# Power_Management.net
KiCad netlist of a schematic drawn in Altium Designer
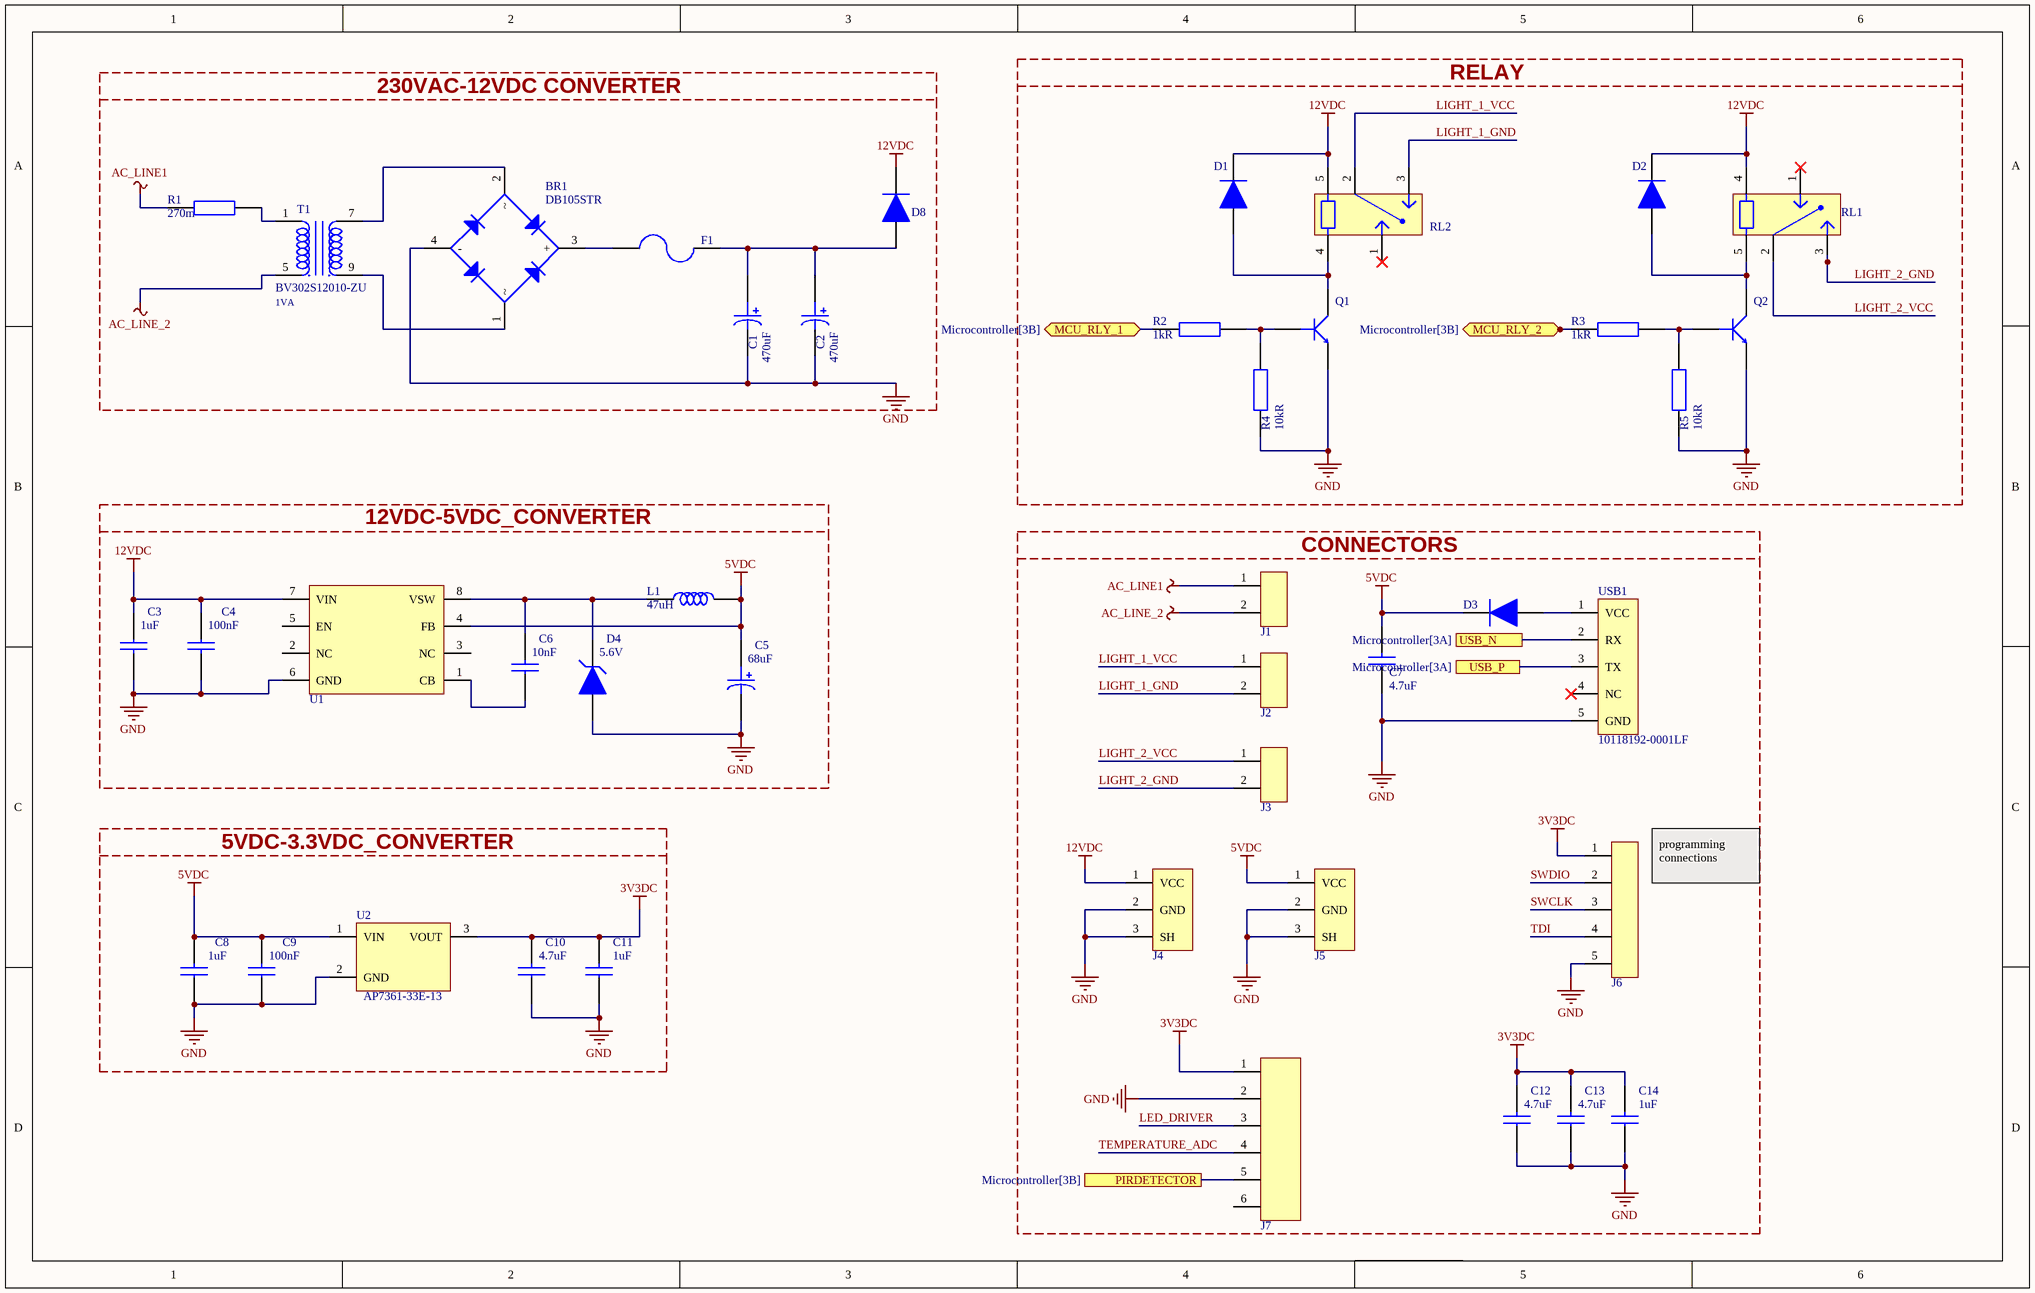
[diagram p0: Power Management.SchDoc]

(export (version "E")
  (design (tool "Eeschema 10.0.6"))
  (components
    (comp (ref "BR1")
      (value "DB105STR")
      (footprint "DB105STR")
      (description "Bridge Rect 1PHASE 600V 1A Db-s")
      (fields
        (field (name "MANUFACTURER") "Sangdest Microelectronics")
        (field (name "MANUFACTURER PART NUMBER") "DB105S")
        (field (name "DESIGNED BY") "Mustafa")
      )
      (libsource (lib "Mustafa_Library") (part "DB105STR"))
    )
    (comp (ref "C1")
      (value "ESH477M050AH4AA")
      (footprint "CAP_RADIAL_D10_P5")
      (description "CAP ALU ELEC 470uF 50V RADIAL")
      (fields
        (field (name "MANUFACTURER") "KEMET")
        (field (name "TOLERANCE") "20%")
        (field (name "CAPACITANCE") "470uF")
        (field (name "DESIGNED BY") "BERK")
      )
      (libsource (lib "Mustafa_Library") (part "CAP ALU ELEC 470uF 50V"))
    )
    (comp (ref "C2")
      (value "ESH477M050AH4AA")
      (footprint "CAP_RADIAL_D10_P5")
      (description "CAP ALU ELEC 470uF 50V RADIAL")
      (fields
        (field (name "MANUFACTURER") "KEMET")
        (field (name "TOLERANCE") "20%")
        (field (name "CAPACITANCE") "470uF")
        (field (name "DESIGNED BY") "BERK")
      )
      (libsource (lib "Mustafa_Library") (part "CAP ALU ELEC 470uF 50V"))
    )
    (comp (ref "C3")
      (value "CL21B105KBFNNNE")
      (footprint "CAP_0805")
      (description "CAP CER 1uF %10 0805")
      (fields
        (field (name "MANUFACTURER") "Samsung")
        (field (name "TOLERANCE") "10%")
        (field (name "CAPACITANCE") "1uF")
        (field (name "DESIGNED BY") "Mustafa")
      )
      (libsource (lib "Mustafa_Library") (part "CAP CER 1uF 0805"))
    )
    (comp (ref "C4")
      (value "CL21B104KBCNNNC")
      (footprint "CAP_0805")
      (description "CAP CER 100nF %10 0805")
      (fields
        (field (name "MANUFACTURER") "Samsung")
        (field (name "TOLERANCE") "10%")
        (field (name "CAPACITANCE") "100nF")
        (field (name "DESIGNED BY") "Mustafa")
      )
      (libsource (lib "Mustafa_Library") (part "CAP CER 100nF 0805"))
    )
    (comp (ref "C5")
      (value "EEV686M035A9HAA")
      (footprint "CAP_EEVseries")
      (description "Cap Aluminum Lytic 68uF 35V 20% (6.3 X 7.7mm) SMD 280mA 2000h 105C T/R")
      (fields
        (field (name "MANUFACTURER") "KEMET")
        (field (name "TOLERANCE") "20%")
        (field (name "CAPACITANCE") "68uF")
      )
      (libsource (lib "Mustafa_Library") (part "CAP ALU 68uF"))
    )
    (comp (ref "C6")
      (value "0603B103K160CT")
      (footprint "CAP_0603")
      (description "CAP CER 10nF %10 0603")
      (fields
        (field (name "MANUFACTURER") "Walsin Technologies")
        (field (name "TOLERANCE") "10%")
        (field (name "CAPACITANCE") "10nF")
        (field (name "DESIGNED BY") "Mustafa")
      )
      (libsource (lib "Mustafa_Library") (part "CAP CER 10nF 0603"))
    )
    (comp (ref "C7")
      (value "CL21A475KAQNNNE")
      (footprint "CAP_0805")
      (description "CAP CER 4.7uF %10 0805")
      (fields
        (field (name "MANUFACTURER") "Samsung")
        (field (name "TOLERANCE") "10%")
        (field (name "CAPACITANCE") "4.7uF")
        (field (name "DESIGNED BY") "Mustafa")
      )
      (libsource (lib "Mustafa_Library") (part "CAP CER 4.7uF 0805"))
    )
    (comp (ref "C8")
      (value "CL21B105KBFNNNE")
      (footprint "CAP_0805")
      (description "CAP CER 1uF %10 0805")
      (fields
        (field (name "MANUFACTURER") "Samsung")
        (field (name "TOLERANCE") "10%")
        (field (name "CAPACITANCE") "1uF")
        (field (name "DESIGNED BY") "Mustafa")
      )
      (libsource (lib "Mustafa_Library") (part "CAP CER 1uF 0805"))
    )
    (comp (ref "C9")
      (value "CL21B104KBCNNNC")
      (footprint "CAP_0805")
      (description "CAP CER 100nF %10 0805")
      (fields
        (field (name "MANUFACTURER") "Samsung")
        (field (name "TOLERANCE") "10%")
        (field (name "CAPACITANCE") "100nF")
        (field (name "DESIGNED BY") "Mustafa")
      )
      (libsource (lib "Mustafa_Library") (part "CAP CER 100nF 0805"))
    )
    (comp (ref "C10")
      (value "CL21A475KAQNNNE")
      (footprint "CAP_0805")
      (description "CAP CER 4.7uF %10 0805")
      (fields
        (field (name "MANUFACTURER") "Samsung")
        (field (name "TOLERANCE") "10%")
        (field (name "CAPACITANCE") "4.7uF")
        (field (name "DESIGNED BY") "Mustafa")
      )
      (libsource (lib "Mustafa_Library") (part "CAP CER 4.7uF 0805"))
    )
    (comp (ref "C11")
      (value "CL21B105KBFNNNE")
      (footprint "CAP_0805")
      (description "CAP CER 1uF %10 0805")
      (fields
        (field (name "MANUFACTURER") "Samsung")
        (field (name "TOLERANCE") "10%")
        (field (name "CAPACITANCE") "1uF")
        (field (name "DESIGNED BY") "Mustafa")
      )
      (libsource (lib "Mustafa_Library") (part "CAP CER 1uF 0805"))
    )
    (comp (ref "C12")
      (value "CL21A475KAQNNNE")
      (footprint "CAP_0805")
      (description "CAP CER 4.7uF %10 0805")
      (fields
        (field (name "MANUFACTURER") "Samsung")
        (field (name "TOLERANCE") "10%")
        (field (name "CAPACITANCE") "4.7uF")
        (field (name "DESIGNED BY") "Mustafa")
      )
      (libsource (lib "Mustafa_Library") (part "CAP CER 4.7uF 0805"))
    )
    (comp (ref "C13")
      (value "CL21A475KAQNNNE")
      (footprint "CAP_0805")
      (description "CAP CER 4.7uF %10 0805")
      (fields
        (field (name "MANUFACTURER") "Samsung")
        (field (name "TOLERANCE") "10%")
        (field (name "CAPACITANCE") "4.7uF")
        (field (name "DESIGNED BY") "Mustafa")
      )
      (libsource (lib "Mustafa_Library") (part "CAP CER 4.7uF 0805"))
    )
    (comp (ref "C14")
      (value "CL21B105KBFNNNE")
      (footprint "CAP_0805")
      (description "CAP CER 1uF %10 0805")
      (fields
        (field (name "MANUFACTURER") "Samsung")
        (field (name "TOLERANCE") "10%")
        (field (name "CAPACITANCE") "1uF")
        (field (name "DESIGNED BY") "Mustafa")
      )
      (libsource (lib "Mustafa_Library") (part "CAP CER 1uF 0805"))
    )
    (comp (ref "D1")
      (value "1N4148WS")
      (footprint "SOD323F")
      (description "Diode, Single, 75 V, 150 mA, 1 V, 4 ns")
      (fields
        (field (name "MANUFACTURER") "ON Semiconductor / Fairchild")
        (field (name "DESIGNED BY") "BERK")
      )
      (libsource (lib "Mustafa_Library") (part "1N4148WS"))
    )
    (comp (ref "D2")
      (value "1N4148WS")
      (footprint "SOD323F")
      (description "Diode, Single, 75 V, 150 mA, 1 V, 4 ns")
      (fields
        (field (name "MANUFACTURER") "ON Semiconductor / Fairchild")
        (field (name "DESIGNED BY") "BERK")
      )
      (libsource (lib "Mustafa_Library") (part "1N4148WS"))
    )
    (comp (ref "D3")
      (value "1N4148WS")
      (footprint "SOD323F")
      (description "Diode, Single, 75 V, 150 mA, 1 V, 4 ns")
      (fields
        (field (name "MANUFACTURER") "ON Semiconductor / Fairchild")
        (field (name "DESIGNED BY") "BERK")
      )
      (libsource (lib "Mustafa_Library") (part "1N4148WS"))
    )
    (comp (ref "D4")
      (value "1SMB5919BT3G")
      (footprint "SMB")
      (description "Diode Zener Single 5.6V 5% 3W 2-Pin SMB T/R")
      (fields
        (field (name "MANUFACTURER") "ON Semiconductor")
        (field (name "TOLERANCE") "5%")
        (field (name "WORKING VOLTAGE") "5.6V")
        (field (name "DESIGNED BY") "Mustafa")
      )
      (libsource (lib "Mustafa_Library") (part "1SMB5919BT3G"))
    )
    (comp (ref "D8")
      (value "1N4148WS")
      (footprint "SOD323F")
      (description "Diode, Single, 75 V, 150 mA, 1 V, 4 ns")
      (fields
        (field (name "MANUFACTURER") "ON Semiconductor / Fairchild")
        (field (name "DESIGNED BY") "BERK")
      )
      (libsource (lib "Mustafa_Library") (part "1N4148WS"))
    )
    (comp (ref "F1")
      (value "3413.0216.22")
      (footprint "3413.0216.22 (sigorta)")
      (description "FUSE BRD MNT 1A 32VAC 63VDC 1206")
      (fields (field (name "MANUFACTURER") "Schurter") (field (name "DESIGNED BY") "BERK"))
      (libsource (lib "Mustafa_Library") (part "FUSE 3413.0216.22"))
    )
    (comp (ref "J1")
      (value "TBP01R1-508-02BE")
      (footprint "TBP01R1-508")
      (description "Conn Shrouded Header HDR 2 POS 5.08mm Solder RA Side Entry Thru-Hole Bag")
      (fields (field (name "MANUFACTURER") "CUI") (field (name "DESIGNED BY") "BERK"))
      (libsource (lib "Mustafa_Library") (part "TBP01R1-508-02BE"))
    )
    (comp (ref "J2")
      (value "TBP01R1-508-02BE")
      (footprint "TBP01R1-508")
      (description "Conn Shrouded Header HDR 2 POS 5.08mm Solder RA Side Entry Thru-Hole Bag")
      (fields (field (name "MANUFACTURER") "CUI") (field (name "DESIGNED BY") "BERK"))
      (libsource (lib "Mustafa_Library") (part "TBP01R1-508-02BE"))
    )
    (comp (ref "J3")
      (value "TBP01R1-508-02BE")
      (footprint "TBP01R1-508")
      (description "Conn Shrouded Header HDR 2 POS 5.08mm Solder RA Side Entry Thru-Hole Bag")
      (fields (field (name "MANUFACTURER") "CUI") (field (name "DESIGNED BY") "BERK"))
      (libsource (lib "Mustafa_Library") (part "TBP01R1-508-02BE"))
    )
    (comp (ref "J4")
      (value "PJ-037AH-SMT-TR")
      (footprint "JACK")
      (description "DC Power Connectors Power Jacks")
      (fields (field (name "MANUFACTURER") "CUI") (field (name "DESIGNED BY") "BERK"))
      (libsource (lib "Mustafa_Library") (part "PJ-037AH-SMT-TR"))
    )
    (comp (ref "J5")
      (value "PJ-037AH-SMT-TR")
      (footprint "JACK")
      (description "DC Power Connectors Power Jacks")
      (fields (field (name "MANUFACTURER") "CUI") (field (name "DESIGNED BY") "BERK"))
      (libsource (lib "Mustafa_Library") (part "PJ-037AH-SMT-TR"))
    )
    (comp (ref "J6")
      (value "SMH-105-02-L-S")
      (footprint "PINHEADER1X5_RA")
      (description ".100 C.L. HORIZONTAL SMT SOCKET")
      (fields (field (name "MANUFACTURER") "Samtec") (field (name "DESIGNED BY") "BERK"))
      (libsource (lib "Mustafa_Library") (part "SMH-105-02-L-S"))
    )
    (comp (ref "J7")
      (value "64800611622")
      (footprint "64800611622")
      (description "1.50mm 6PIN Connector")
      (fields (field (name "MANUFACTURER") "Wurth Electronics"))
      (libsource (lib "Mustafa_Library") (part "64800611622_conn_6pin"))
    )
    (comp (ref "L1")
      (value "78438335470")
      (footprint "IND_1212")
      (description "FIXED IND 47UH 390MA 2.3 OHM SMD")
      (fields
        (field (name "MANUFACTURER") "Wurth Electronics")
        (field (name "TOLERANCE") "30%")
        (field (name "INDUCTANCE") "47uH")
        (field (name "DESIGNED BY") "Mustafa")
      )
      (libsource (lib "Mustafa_Library") (part "IND 47uH"))
    )
    (comp (ref "Q1")
      (value "MMBT3904-7-F")
      (footprint "SOT-23F")
      (description "Transistor General Purpose BJT NPN 40 Volt 0.2A Automotive 3-Pin SOT-23")
      (fields (field (name "MANUFACTURER") "Diodes Zetex") (field (name "DESIGNED BY") "Mustafa"))
      (libsource (lib "Mustafa_Library") (part "MMBT3904-7-F"))
    )
    (comp (ref "Q2")
      (value "MMBT3904-7-F")
      (footprint "SOT-23F")
      (description "Transistor General Purpose BJT NPN 40 Volt 0.2A Automotive 3-Pin SOT-23")
      (fields (field (name "MANUFACTURER") "Diodes Zetex") (field (name "DESIGNED BY") "Mustafa"))
      (libsource (lib "Mustafa_Library") (part "MMBT3904-7-F"))
    )
    (comp (ref "R1")
      (value "5WD27")
      (footprint "RES_AXIAL_W")
      (description "Resistor 5 Watt Cermet Wirewound Flameproof .27 Ohm 5% Axial Lead")
      (fields
        (field (name "MANUFACTURER") "NTE Electronics")
        (field (name "TOLERANCE") "5%")
        (field (name "RESISTANCE") "270m")
        (field (name "DESIGNED BY") "Mustafa")
      )
      (libsource (lib "Mustafa_Library") (part "5WD27"))
    )
    (comp (ref "R2")
      (value "RC0603FR-0710KL")
      (footprint "RES_0603")
      (description "RES 1K %1 OHM 0603 SMD")
      (fields
        (field (name "MANUFACTURER") "Yageo")
        (field (name "MANUFACTURER PART NUMBER") "RC0603JR-071KL")
        (field (name "RESISTANCE") "1kR")
        (field (name "DESIGNED BY") "BERK")
      )
      (libsource (lib "Mustafa_Library") (part "RES 1K OHM 0603"))
    )
    (comp (ref "R3")
      (value "RC0603FR-0710KL")
      (footprint "RES_0603")
      (description "RES 1K %1 OHM 0603 SMD")
      (fields
        (field (name "MANUFACTURER") "Yageo")
        (field (name "MANUFACTURER PART NUMBER") "RC0603JR-071KL")
        (field (name "RESISTANCE") "1kR")
        (field (name "DESIGNED BY") "BERK")
      )
      (libsource (lib "Mustafa_Library") (part "RES 1K OHM 0603"))
    )
    (comp (ref "R4")
      (value "10kR")
      (footprint "RES_0603")
      (description "RES 10K %1 OHM 0603 SMD")
      (fields
        (field (name "MANUFACTURER") "Yageo")
        (field (name "MANUFACTURER PART NUMBER") "RC0603FR-0710KL")
        (field (name "DESIGNED BY") "Mustafa")
      )
      (libsource (lib "Mustafa_Library") (part "RES 10K OHM 0603"))
    )
    (comp (ref "R5")
      (value "10kR")
      (footprint "RES_0603")
      (description "RES 10K %1 OHM 0603 SMD")
      (fields
        (field (name "MANUFACTURER") "Yageo")
        (field (name "MANUFACTURER PART NUMBER") "RC0603FR-0710KL")
        (field (name "DESIGNED BY") "Mustafa")
      )
      (libsource (lib "Mustafa_Library") (part "RES 10K OHM 0603"))
    )
    (comp (ref "RL1")
      (value "ALQ112")
      (footprint "ALQ112")
      (description "General Purpose Relay SPDT (1 Form C) 12VDC Coil Through Hole")
      (fields (field (name "MANUFACTURER") "Panasonic") (field (name "DESIGNED BY") "Mustafa"))
      (libsource (lib "") (part "ALQ112_1"))
    )
    (comp (ref "RL2")
      (value "ALQ112")
      (footprint "ALQ112")
      (description "General Purpose Relay SPDT (1 Form C) 12VDC Coil Through Hole")
      (fields (field (name "MANUFACTURER") "Panasonic") (field (name "DESIGNED BY") "Mustafa"))
      (libsource (lib "Mustafa_Library") (part "ALQ112"))
    )
    (comp (ref "T1")
      (value "BV302S12010-ZU")
      (footprint "BV302S")
      (description "230-12V Transformer 1VA")
      (fields
        (field (name "MANUFACTURER PRODUCT NUMBER") "BV302S12010-ZU")
        (field (name "MANUFACTURER") "Zettler Magnetics")
        (field (name "RATED POWER") "1VA")
        (field (name "DESIGNED BY") "Mustafa")
      )
      (libsource (lib "Mustafa_Library") (part "BV302S12010-ZU"))
    )
    (comp (ref "U1")
      (value "LM2675MX-12/NOPB")
      (footprint "SOIC-8")
      (description "SIMPLE SWITCHER® 6.5V to 40V, 1A Low Component Count Step-Down Regulator 8-SOIC -40 to 125")
      (fields
        (field (name "MANUFACTURER") "TI National Semiconductor")
        (field (name "DESIGNED BY") "Mustafa")
      )
      (libsource (lib "Mustafa_Library") (part "LM2675MX-12/NOPB"))
    )
    (comp (ref "U2")
      (value "AP7361-33E-13")
      (footprint "SOT-223")
      (description "AP7361 Series 3.3 V 1 A Low SMT Dropout Fixed-Mode Regulator - SOT-223")
      (fields (field (name "MANUFACTURER") "Diodes") (field (name "DESIGNED BY") "Mustafa"))
      (libsource (lib "Mustafa_Library") (part "AP7361-33E-13"))
    )
    (comp (ref "USB1")
      (value "10118192-0001LF")
      (footprint "MICRO_B_USB")
      (description "CONN RCPT USB2.0 MICRO B SMD R/A")
      (fields (field (name "MANUFACTURER") "Amphenol FCI") (field (name "DESIGNED BY") "BERK"))
      (libsource (lib "Mustafa_Library") (part "Micro B USB Connector"))
    )
  )
  (nets
    (net (code "1") (name "/LED_DRIVER") (class "Default") (node (ref "J7") (pin "3") (pintype "power_in")))
    (net (code "2") (name "/LIGHT_1_GND") (class "Default")
      (node (ref "J2") (pin "2") (pinfunction "2_2") (pintype "power_in"))
      (node (ref "RL2") (pin "3") (pinfunction "3_3") (pintype "passive"))
    )
    (net (code "3") (name "/LIGHT_1_VCC") (class "Default")
      (node (ref "J2") (pin "1") (pinfunction "1_1") (pintype "power_in"))
      (node (ref "RL2") (pin "2") (pinfunction "2_2") (pintype "passive"))
    )
    (net (code "4") (name "/LIGHT_2_GND") (class "Default")
      (node (ref "J3") (pin "2") (pinfunction "2_2") (pintype "power_in"))
      (node (ref "RL1") (pin "3") (pinfunction "3_3") (pintype "passive"))
    )
    (net (code "5") (name "/LIGHT_2_VCC") (class "Default")
      (node (ref "J3") (pin "1") (pinfunction "1_1") (pintype "power_in"))
      (node (ref "RL1") (pin "2") (pinfunction "2_2") (pintype "passive"))
    )
    (net (code "6") (name "/MCU_RLY_1") (class "Default")
      (node (ref "R2") (pin "1") (pinfunction "1_1") (pintype "passive"))
    )
    (net (code "7") (name "/MCU_RLY_2") (class "Default")
      (node (ref "R3") (pin "1") (pinfunction "1_1") (pintype "passive"))
    )
    (net (code "8") (name "/PIRDETECTOR") (class "Default") (node (ref "J7") (pin "5") (pintype "power_in")))
    (net (code "9") (name "/SWCLK") (class "Default")
      (node (ref "J6") (pin "3") (pinfunction "3_3") (pintype "power_in"))
    )
    (net (code "10") (name "/SWDIO") (class "Default")
      (node (ref "J6") (pin "2") (pinfunction "2_2") (pintype "power_in"))
    )
    (net (code "11") (name "/TDI") (class "Default")
      (node (ref "J6") (pin "4") (pinfunction "4_4") (pintype "power_in"))
    )
    (net (code "12") (name "/TEMPERATURE_ADC") (class "Default")
      (node (ref "J7") (pin "4") (pintype "power_in"))
    )
    (net (code "13") (name "/USB_N") (class "Default")
      (node (ref "USB1") (pin "2") (pinfunction "RX_2") (pintype "power_in"))
    )
    (net (code "14") (name "/USB_P") (class "Default")
      (node (ref "USB1") (pin "3") (pinfunction "TX_3") (pintype "power_in"))
    )
    (net (code "15") (name "3V3DC") (class "Default")
      (node (ref "C10") (pin "2") (pinfunction "2_2") (pintype "passive"))
      (node (ref "C11") (pin "2") (pinfunction "2_2") (pintype "passive"))
      (node (ref "C12") (pin "2") (pinfunction "2_2") (pintype "passive"))
      (node (ref "C13") (pin "2") (pinfunction "2_2") (pintype "passive"))
      (node (ref "C14") (pin "2") (pinfunction "2_2") (pintype "passive"))
      (node (ref "J6") (pin "1") (pinfunction "1_1") (pintype "power_in"))
      (node (ref "J7") (pin "1") (pintype "power_in"))
      (node (ref "U2") (pin "3") (pinfunction "VOUT_3") (pintype "passive"))
    )
    (net (code "16") (name "5VDC") (class "Default")
      (node (ref "C5") (pin "1") (pinfunction "1_1") (pintype "passive"))
      (node (ref "C7") (pin "2") (pinfunction "2_2") (pintype "passive"))
      (node (ref "C8") (pin "2") (pinfunction "2_2") (pintype "passive"))
      (node (ref "C9") (pin "2") (pinfunction "2_2") (pintype "passive"))
      (node (ref "D3") (pin "1") (pinfunction "1_1") (pintype "power_in"))
      (node (ref "J5") (pin "1") (pinfunction "VCC_1") (pintype "power_in"))
      (node (ref "L1") (pin "2") (pinfunction "2_2") (pintype "passive"))
      (node (ref "U1") (pin "4") (pinfunction "FB_4") (pintype "passive"))
      (node (ref "U2") (pin "1") (pinfunction "VIN_1") (pintype "passive"))
    )
    (net (code "17") (name "12VDC") (class "Default")
      (node (ref "C3") (pin "1") (pinfunction "1_1") (pintype "passive"))
      (node (ref "C4") (pin "1") (pinfunction "1_1") (pintype "passive"))
      (node (ref "D1") (pin "1") (pinfunction "1_1") (pintype "power_in"))
      (node (ref "D2") (pin "1") (pinfunction "1_1") (pintype "power_in"))
      (node (ref "D8") (pin "1") (pinfunction "1_1") (pintype "power_in"))
      (node (ref "J4") (pin "1") (pinfunction "VCC_1") (pintype "power_in"))
      (node (ref "RL1") (pin "4") (pinfunction "4_4") (pintype "passive"))
      (node (ref "RL2") (pin "5") (pinfunction "5_5") (pintype "passive"))
      (node (ref "U1") (pin "7") (pinfunction "VIN_7") (pintype "passive"))
    )
    (net (code "18") (name "AC_LINE1") (class "Default")
      (node (ref "J1") (pin "1") (pinfunction "1_1") (pintype "power_in"))
      (node (ref "R1") (pin "1") (pinfunction "1_1") (pintype "passive"))
    )
    (net (code "19") (name "AC_LINE_2") (class "Default")
      (node (ref "J1") (pin "2") (pinfunction "2_2") (pintype "power_in"))
      (node (ref "T1") (pin "5") (pinfunction "5_5") (pintype "passive"))
    )
    (net (code "20") (name "GND") (class "Default")
      (node (ref "BR1") (pin "4") (pinfunction "-_4") (pintype "passive"))
      (node (ref "C1") (pin "2") (pinfunction "2_2") (pintype "passive"))
      (node (ref "C10") (pin "1") (pinfunction "1_1") (pintype "passive"))
      (node (ref "C11") (pin "1") (pinfunction "1_1") (pintype "passive"))
      (node (ref "C12") (pin "1") (pinfunction "1_1") (pintype "passive"))
      (node (ref "C13") (pin "1") (pinfunction "1_1") (pintype "passive"))
      (node (ref "C14") (pin "1") (pinfunction "1_1") (pintype "passive"))
      (node (ref "C2") (pin "2") (pinfunction "2_2") (pintype "passive"))
      (node (ref "C3") (pin "2") (pinfunction "2_2") (pintype "passive"))
      (node (ref "C4") (pin "2") (pinfunction "2_2") (pintype "passive"))
      (node (ref "C5") (pin "2") (pinfunction "2_2") (pintype "passive"))
      (node (ref "C7") (pin "1") (pinfunction "1_1") (pintype "passive"))
      (node (ref "C8") (pin "1") (pinfunction "1_1") (pintype "passive"))
      (node (ref "C9") (pin "1") (pinfunction "1_1") (pintype "passive"))
      (node (ref "D4") (pin "A") (pinfunction "A_A") (pintype "passive"))
      (node (ref "J4") (pin "2") (pinfunction "GND_2") (pintype "power_in"))
      (node (ref "J4") (pin "3") (pinfunction "SH_3") (pintype "power_in"))
      (node (ref "J5") (pin "2") (pinfunction "GND_2") (pintype "power_in"))
      (node (ref "J5") (pin "3") (pinfunction "SH_3") (pintype "power_in"))
      (node (ref "J6") (pin "5") (pinfunction "5_5") (pintype "power_in"))
      (node (ref "J7") (pin "2") (pintype "power_in"))
      (node (ref "Q1") (pin "2") (pinfunction "E_2") (pintype "power_in"))
      (node (ref "Q2") (pin "2") (pinfunction "E_2") (pintype "power_in"))
      (node (ref "R4") (pin "1") (pinfunction "1_1") (pintype "passive"))
      (node (ref "R5") (pin "1") (pinfunction "1_1") (pintype "passive"))
      (node (ref "U1") (pin "6") (pinfunction "GND_6") (pintype "passive"))
      (node (ref "U2") (pin "2") (pinfunction "GND_2") (pintype "passive"))
      (node (ref "USB1") (pin "5") (pinfunction "GND_5") (pintype "power_in"))
    )
    (net (code "21") (name "Net-(BR1-+)") (class "Default")
      (node (ref "BR1") (pin "3") (pinfunction "+_3") (pintype "passive"))
      (node (ref "F1") (pin "1") (pinfunction "1_1") (pintype "passive"))
    )
    (net (code "22") (name "Net-(BR1-~-Pad1)") (class "Default")
      (node (ref "BR1") (pin "1") (pinfunction "~_1") (pintype "passive"))
      (node (ref "T1") (pin "9") (pinfunction "9_9") (pintype "passive"))
    )
    (net (code "23") (name "Net-(BR1-~-Pad2)") (class "Default")
      (node (ref "BR1") (pin "2") (pinfunction "~_2") (pintype "passive"))
      (node (ref "T1") (pin "7") (pinfunction "7_7") (pintype "passive"))
    )
    (net (code "24") (name "Net-(C1-Pad1)") (class "Default")
      (node (ref "C1") (pin "1") (pinfunction "1_1") (pintype "passive"))
      (node (ref "C2") (pin "1") (pinfunction "1_1") (pintype "passive"))
      (node (ref "D8") (pin "2") (pinfunction "2_2") (pintype "power_in"))
      (node (ref "F1") (pin "2") (pinfunction "2_2") (pintype "passive"))
    )
    (net (code "25") (name "Net-(Q1-B)") (class "Default")
      (node (ref "Q1") (pin "1") (pinfunction "B_1") (pintype "power_in"))
      (node (ref "R2") (pin "2") (pinfunction "2_2") (pintype "passive"))
      (node (ref "R4") (pin "2") (pinfunction "2_2") (pintype "passive"))
    )
    (net (code "26") (name "Net-(Q1-C)") (class "Default")
      (node (ref "D1") (pin "2") (pinfunction "2_2") (pintype "power_in"))
      (node (ref "Q1") (pin "3") (pinfunction "C_3") (pintype "power_in"))
      (node (ref "RL2") (pin "4") (pinfunction "4_4") (pintype "passive"))
    )
    (net (code "27") (name "Net-(Q2-B)") (class "Default")
      (node (ref "Q2") (pin "1") (pinfunction "B_1") (pintype "power_in"))
      (node (ref "R3") (pin "2") (pinfunction "2_2") (pintype "passive"))
      (node (ref "R5") (pin "2") (pinfunction "2_2") (pintype "passive"))
    )
    (net (code "28") (name "Net-(Q2-C)") (class "Default")
      (node (ref "D2") (pin "2") (pinfunction "2_2") (pintype "power_in"))
      (node (ref "Q2") (pin "3") (pinfunction "C_3") (pintype "power_in"))
      (node (ref "RL1") (pin "5") (pinfunction "5_5") (pintype "passive"))
    )
    (net (code "29") (name "Net-(R1-Pad2)") (class "Default")
      (node (ref "R1") (pin "2") (pinfunction "2_2") (pintype "passive"))
      (node (ref "T1") (pin "1") (pinfunction "1_1") (pintype "passive"))
    )
    (net (code "30") (name "Net-(U1-CB)") (class "Default")
      (node (ref "C6") (pin "1") (pinfunction "1_1") (pintype "passive"))
      (node (ref "U1") (pin "1") (pinfunction "CB_1") (pintype "passive"))
    )
    (net (code "31") (name "Net-(U1-VSW)") (class "Default")
      (node (ref "C6") (pin "2") (pinfunction "2_2") (pintype "passive"))
      (node (ref "D4") (pin "C") (pinfunction "C_C") (pintype "passive"))
      (node (ref "L1") (pin "1") (pinfunction "1_1") (pintype "passive"))
      (node (ref "U1") (pin "8") (pinfunction "VSW_8") (pintype "passive"))
    )
    (net (code "32") (name "Net-(USB1-VCC)") (class "Default")
      (node (ref "D3") (pin "2") (pinfunction "2_2") (pintype "power_in"))
      (node (ref "USB1") (pin "1") (pinfunction "VCC_1") (pintype "power_in"))
    )
    (net (code "33") (name "unconnected-(J7-Pad6)") (class "Default")
      (node (ref "J7") (pin "6") (pintype "power_in"))
    )
    (net (code "34") (name "unconnected-(RL1-Pad1)") (class "Default")
      (node (ref "RL1") (pin "1") (pinfunction "1_1") (pintype "passive+no_connect"))
    )
    (net (code "35") (name "unconnected-(RL2-Pad1)") (class "Default")
      (node (ref "RL2") (pin "1") (pinfunction "1_1") (pintype "passive+no_connect"))
    )
    (net (code "36") (name "unconnected-(U1-EN-Pad5)") (class "Default")
      (node (ref "U1") (pin "5") (pinfunction "EN_5") (pintype "passive"))
    )
    (net (code "37") (name "unconnected-(U1-NC-Pad2)") (class "Default")
      (node (ref "U1") (pin "2") (pinfunction "NC_2") (pintype "passive"))
    )
    (net (code "38") (name "unconnected-(U1-NC-Pad3)") (class "Default")
      (node (ref "U1") (pin "3") (pinfunction "NC_3") (pintype "passive"))
    )
    (net (code "39") (name "unconnected-(USB1-NC-Pad4)") (class "Default")
      (node (ref "USB1") (pin "4") (pinfunction "NC_4") (pintype "power_in+no_connect"))
    )
  )
)
